# 28pins_sch.net
KiCad netlist of a schematic drawn in Altium Designer
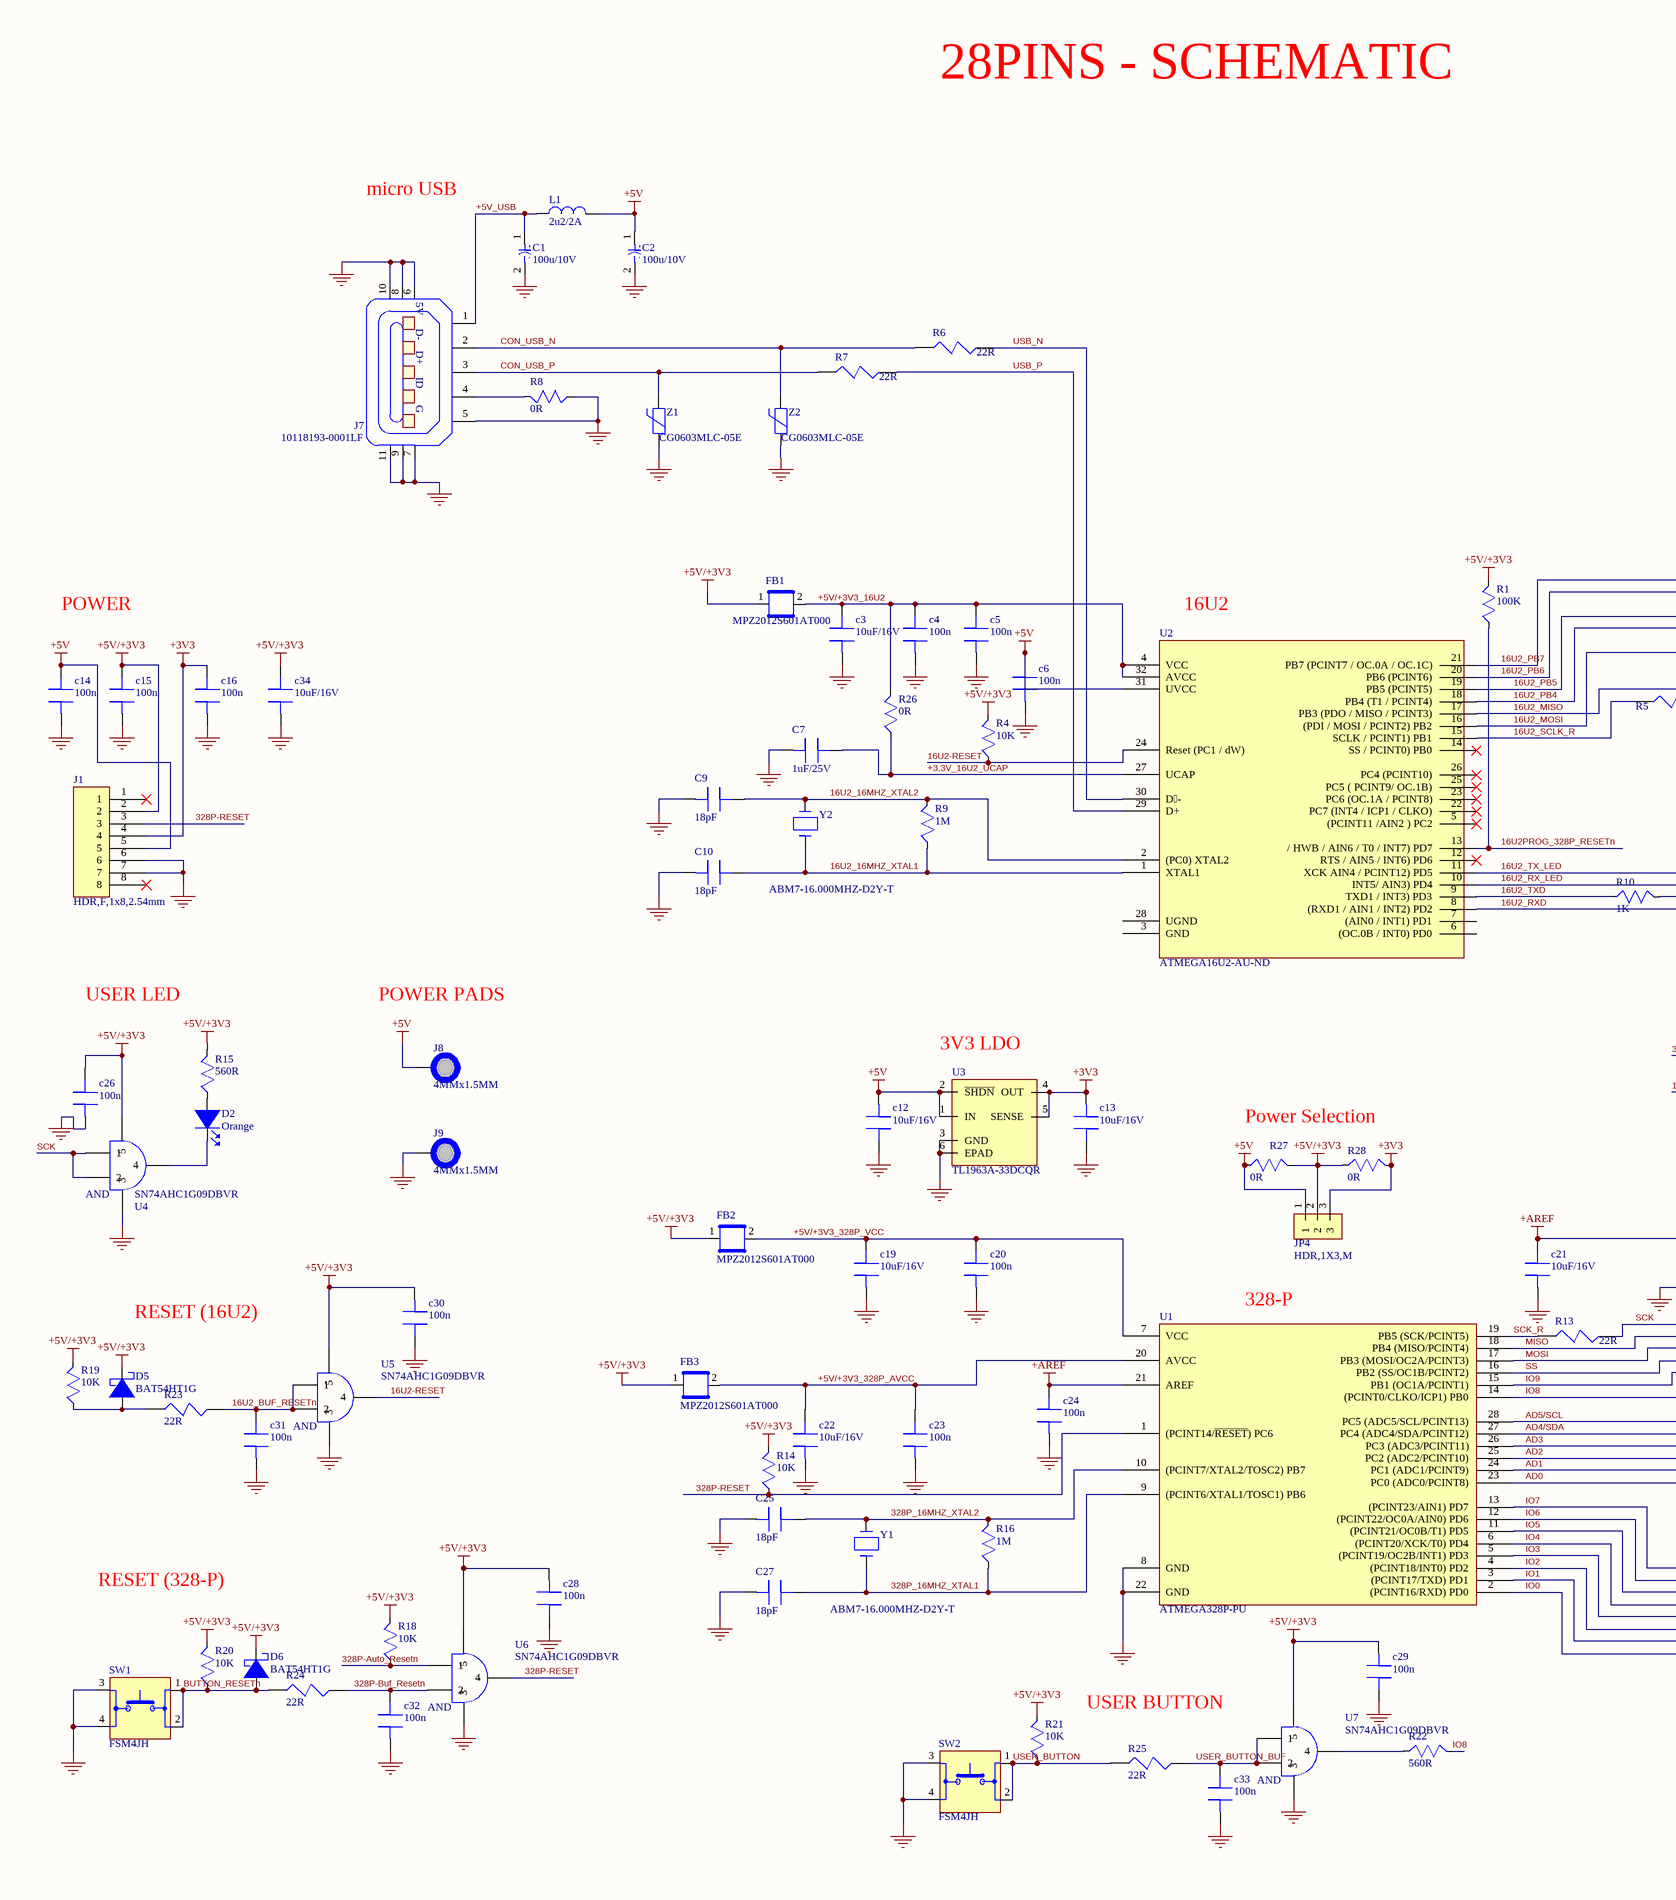
[diagram p0: 28pins_sch.SchDoc, left]
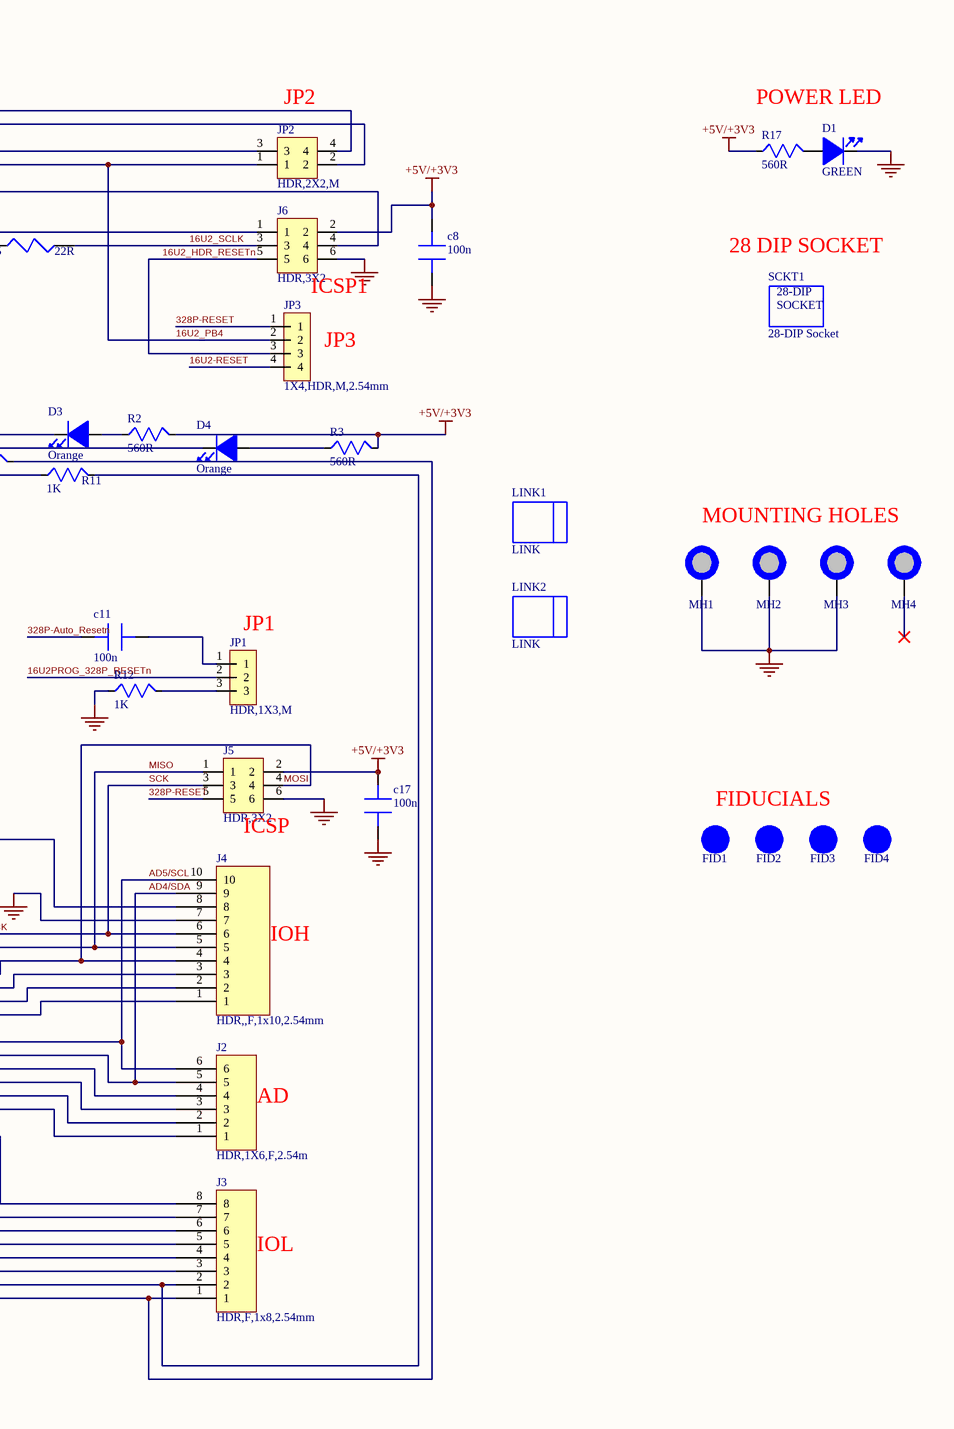
[diagram p1: 28pins_sch.SchDoc, right]

(export (version "E")
  (design (tool "Eeschema 10.0.6"))
  (components
    (comp (ref "C1")
      (value "100u/10V")
      (footprint "C_ALUM")
      (fields
        (field (name "MANUFACTURER") "Panasonic")
        (field (name "MANUFACTURER PART NUMBER") "EEE-1AA101WR")
      )
      (libsource (lib "28pins_Schlib1") (part "EEE-1AA101WR"))
    )
    (comp (ref "C2")
      (value "100u/10V")
      (footprint "C_ALUM")
      (fields
        (field (name "MANUFACTURER") "Panasonic")
        (field (name "MANUFACTURER PART NUMBER") "EEE-1AA101WR")
      )
      (libsource (lib "28pins_Schlib1") (part "EEE-1AA101WR"))
    )
    (comp (ref "c3")
      (value "10uF/16V")
      (footprint "X5R 0805")
      (fields
        (field (name "MANUFACTURER") "TDK")
        (field (name "MANUFACTURER PART NUMBER") "C2012X5R1C106K085AC")
      )
      (libsource (lib "28pins_Schlib1") (part "C2012X5R1C106K085AC"))
    )
    (comp (ref "c4")
      (value "100n")
      (footprint "C0805")
      (fields
        (field (name "MANUFACTURER") "Samsung")
        (field (name "MANUFACTURER PART NUMBER") "CL21B104KBCNNNC")
      )
      (libsource (lib "28pins_Schlib1") (part "CL21B104KBCNNNC"))
    )
    (comp (ref "c5")
      (value "100n")
      (footprint "C0805")
      (fields
        (field (name "MANUFACTURER") "Samsung")
        (field (name "MANUFACTURER PART NUMBER") "CL21B104KBCNNNC")
      )
      (libsource (lib "28pins_Schlib1") (part "CL21B104KBCNNNC"))
    )
    (comp (ref "c6")
      (value "100n")
      (footprint "C0805")
      (fields
        (field (name "MANUFACTURER") "Samsung")
        (field (name "MANUFACTURER PART NUMBER") "CL21B104KBCNNNC")
      )
      (libsource (lib "28pins_Schlib1") (part "CL21B104KBCNNNC"))
    )
    (comp (ref "C7")
      (value "1uF/25V")
      (footprint "C0805")
      (fields
        (field (name "MANUFACTURER") "TDK")
        (field (name "MANUFACTURER PART NUMBER") "C2012X5R1E105K125AA")
      )
      (libsource (lib "28pins_Schlib1") (part "C2012X5R1E105K125AA"))
    )
    (comp (ref "c8")
      (value "100n")
      (footprint "C0805")
      (fields
        (field (name "MANUFACTURER") "Samsung")
        (field (name "MANUFACTURER PART NUMBER") "CL21B104KBCNNNC")
      )
      (libsource (lib "28pins_Schlib1") (part "CL21B104KBCNNNC"))
    )
    (comp (ref "C9")
      (value "18pF")
      (footprint "C0805")
      (fields
        (field (name "MANUFACTURER") "KEMET")
        (field (name "MANUFACTURER PART NUMBER") "C0805C180K5RACTU")
      )
      (libsource (lib "28pins_Schlib1") (part "C0805C180K5RACTU"))
    )
    (comp (ref "C10")
      (value "18pF")
      (footprint "C0805")
      (fields
        (field (name "MANUFACTURER") "KEMET")
        (field (name "MANUFACTURER PART NUMBER") "C0805C180K5RACTU")
      )
      (libsource (lib "28pins_Schlib1") (part "C0805C180K5RACTU"))
    )
    (comp (ref "c11")
      (value "100n")
      (footprint "C0805")
      (fields
        (field (name "MANUFACTURER") "Samsung")
        (field (name "MANUFACTURER PART NUMBER") "CL21B104KBCNNNC")
      )
      (libsource (lib "28pins_Schlib1") (part "CL21B104KBCNNNC"))
    )
    (comp (ref "c12")
      (value "10uF/16V")
      (footprint "X5R 0805")
      (fields
        (field (name "MANUFACTURER") "TDK")
        (field (name "MANUFACTURER PART NUMBER") "C2012X5R1C106K085AC")
      )
      (libsource (lib "28pins_Schlib1") (part "C2012X5R1C106K085AC"))
    )
    (comp (ref "c13")
      (value "10uF/16V")
      (footprint "X5R 0805")
      (fields
        (field (name "MANUFACTURER") "TDK")
        (field (name "MANUFACTURER PART NUMBER") "C2012X5R1C106K085AC")
      )
      (libsource (lib "28pins_Schlib1") (part "C2012X5R1C106K085AC"))
    )
    (comp (ref "c14")
      (value "100n")
      (footprint "C0805")
      (fields
        (field (name "MANUFACTURER") "Samsung")
        (field (name "MANUFACTURER PART NUMBER") "CL21B104KBCNNNC")
      )
      (libsource (lib "28pins_Schlib1") (part "CL21B104KBCNNNC"))
    )
    (comp (ref "c15")
      (value "100n")
      (footprint "C0805")
      (fields
        (field (name "MANUFACTURER") "Samsung")
        (field (name "MANUFACTURER PART NUMBER") "CL21B104KBCNNNC")
      )
      (libsource (lib "28pins_Schlib1") (part "CL21B104KBCNNNC"))
    )
    (comp (ref "c16")
      (value "100n")
      (footprint "C0805")
      (fields
        (field (name "MANUFACTURER") "Samsung")
        (field (name "MANUFACTURER PART NUMBER") "CL21B104KBCNNNC")
      )
      (libsource (lib "28pins_Schlib1") (part "CL21B104KBCNNNC"))
    )
    (comp (ref "c17")
      (value "100n")
      (footprint "C0805")
      (fields
        (field (name "MANUFACTURER") "Samsung")
        (field (name "MANUFACTURER PART NUMBER") "CL21B104KBCNNNC")
      )
      (libsource (lib "28pins_Schlib1") (part "CL21B104KBCNNNC"))
    )
    (comp (ref "c19")
      (value "10uF/16V")
      (footprint "X5R 0805")
      (fields
        (field (name "MANUFACTURER") "TDK")
        (field (name "MANUFACTURER PART NUMBER") "C2012X5R1C106K085AC")
      )
      (libsource (lib "28pins_Schlib1") (part "C2012X5R1C106K085AC"))
    )
    (comp (ref "c20")
      (value "100n")
      (footprint "C0805")
      (fields
        (field (name "MANUFACTURER") "Samsung")
        (field (name "MANUFACTURER PART NUMBER") "CL21B104KBCNNNC")
      )
      (libsource (lib "28pins_Schlib1") (part "CL21B104KBCNNNC"))
    )
    (comp (ref "c21")
      (value "10uF/16V")
      (footprint "X5R 0805")
      (fields
        (field (name "MANUFACTURER") "TDK")
        (field (name "MANUFACTURER PART NUMBER") "C2012X5R1C106K085AC")
      )
      (libsource (lib "28pins_Schlib1") (part "C2012X5R1C106K085AC"))
    )
    (comp (ref "c22")
      (value "10uF/16V")
      (footprint "X5R 0805")
      (fields
        (field (name "MANUFACTURER") "TDK")
        (field (name "MANUFACTURER PART NUMBER") "C2012X5R1C106K085AC")
      )
      (libsource (lib "28pins_Schlib1") (part "C2012X5R1C106K085AC"))
    )
    (comp (ref "c23")
      (value "100n")
      (footprint "C0805")
      (fields
        (field (name "MANUFACTURER") "Samsung")
        (field (name "MANUFACTURER PART NUMBER") "CL21B104KBCNNNC")
      )
      (libsource (lib "28pins_Schlib1") (part "CL21B104KBCNNNC"))
    )
    (comp (ref "c24")
      (value "100n")
      (footprint "C0805")
      (fields
        (field (name "MANUFACTURER") "Samsung")
        (field (name "MANUFACTURER PART NUMBER") "CL21B104KBCNNNC")
      )
      (libsource (lib "28pins_Schlib1") (part "CL21B104KBCNNNC"))
    )
    (comp (ref "C25")
      (value "18pF")
      (footprint "C0805")
      (fields
        (field (name "MANUFACTURER") "KEMET")
        (field (name "MANUFACTURER PART NUMBER") "C0805C180K5RACTU")
      )
      (libsource (lib "28pins_Schlib1") (part "C0805C180K5RACTU"))
    )
    (comp (ref "c26")
      (value "100n")
      (footprint "C0805")
      (fields
        (field (name "MANUFACTURER") "Samsung")
        (field (name "MANUFACTURER PART NUMBER") "CL21B104KBCNNNC")
      )
      (libsource (lib "28pins_Schlib1") (part "CL21B104KBCNNNC"))
    )
    (comp (ref "C27")
      (value "18pF")
      (footprint "C0805")
      (fields
        (field (name "MANUFACTURER") "KEMET")
        (field (name "MANUFACTURER PART NUMBER") "C0805C180K5RACTU")
      )
      (libsource (lib "28pins_Schlib1") (part "C0805C180K5RACTU"))
    )
    (comp (ref "c28")
      (value "100n")
      (footprint "C0805")
      (fields
        (field (name "MANUFACTURER") "Samsung")
        (field (name "MANUFACTURER PART NUMBER") "CL21B104KBCNNNC")
      )
      (libsource (lib "28pins_Schlib1") (part "CL21B104KBCNNNC"))
    )
    (comp (ref "c29")
      (value "100n")
      (footprint "C0805")
      (fields
        (field (name "MANUFACTURER") "Samsung")
        (field (name "MANUFACTURER PART NUMBER") "CL21B104KBCNNNC")
      )
      (libsource (lib "28pins_Schlib1") (part "CL21B104KBCNNNC"))
    )
    (comp (ref "c30")
      (value "100n")
      (footprint "C0805")
      (fields
        (field (name "MANUFACTURER") "Samsung")
        (field (name "MANUFACTURER PART NUMBER") "CL21B104KBCNNNC")
      )
      (libsource (lib "28pins_Schlib1") (part "CL21B104KBCNNNC"))
    )
    (comp (ref "c31")
      (value "100n")
      (footprint "C0805")
      (fields
        (field (name "MANUFACTURER") "Samsung")
        (field (name "MANUFACTURER PART NUMBER") "CL21B104KBCNNNC")
      )
      (libsource (lib "28pins_Schlib1") (part "CL21B104KBCNNNC"))
    )
    (comp (ref "c32")
      (value "100n")
      (footprint "C0805")
      (fields
        (field (name "MANUFACTURER") "Samsung")
        (field (name "MANUFACTURER PART NUMBER") "CL21B104KBCNNNC")
      )
      (libsource (lib "28pins_Schlib1") (part "CL21B104KBCNNNC"))
    )
    (comp (ref "c33")
      (value "100n")
      (footprint "C0805")
      (fields
        (field (name "MANUFACTURER") "Samsung")
        (field (name "MANUFACTURER PART NUMBER") "CL21B104KBCNNNC")
      )
      (libsource (lib "28pins_Schlib1") (part "CL21B104KBCNNNC"))
    )
    (comp (ref "c34")
      (value "10uF/16V")
      (footprint "X5R 0805")
      (fields
        (field (name "MANUFACTURER") "TDK")
        (field (name "MANUFACTURER PART NUMBER") "C2012X5R1C106K085AC")
      )
      (libsource (lib "28pins_Schlib1") (part "C2012X5R1C106K085AC"))
    )
    (comp (ref "D1")
      (value "GREEN")
      (footprint "LED_0603")
      (description "Single Color LED")
      (fields
        (field (name "MANUFACTURER") "SunLED")
        (field (name "MANUFACTURER PART NUMBER") "XZCDGK53W-8VF")
      )
      (libsource (lib "28pins_Schlib1") (part "XZCDGK53W-8VF"))
    )
    (comp (ref "D2")
      (value "Orange")
      (footprint "LED_0603")
      (description "Single Color LED Array, Orange, Transparent Clear, 1.2mm")
      (fields (field (name "MANUFACTURER") "Rohm") (field (name "MANUFACTURER PART NUMBER") "SML-311DTT86"))
      (libsource (lib "28pins_Schlib1") (part "SML-311DTT86"))
    )
    (comp (ref "D3")
      (value "Orange")
      (footprint "LED_0603")
      (description "Single Color LED Array, Orange, Transparent Clear, 1.2mm")
      (fields (field (name "MANUFACTURER") "Rohm") (field (name "MANUFACTURER PART NUMBER") "SML-311DTT86"))
      (libsource (lib "28pins_Schlib1") (part "SML-311DTT86"))
    )
    (comp (ref "D4")
      (value "Orange")
      (footprint "LED_0603")
      (description "Single Color LED Array, Orange, Transparent Clear, 1.2mm")
      (fields (field (name "MANUFACTURER") "Rohm") (field (name "MANUFACTURER PART NUMBER") "SML-311DTT86"))
      (libsource (lib "28pins_Schlib1") (part "SML-311DTT86"))
    )
    (comp (ref "D5")
      (value "BAT54HT1G")
      (footprint "SOD323")
      (description "Rectifier Diode, 1 Phase, 1 Element, 0.2A, 30V V(RRM), Silicon")
      (fields (field (name "MANUFACTURER") "ON Semiconductor / Fairchild"))
      (libsource (lib "28pins_Schlib1") (part "BAT54HT1G"))
    )
    (comp (ref "D6")
      (value "BAT54HT1G")
      (footprint "SOD323")
      (description "Rectifier Diode, 1 Phase, 1 Element, 0.2A, 30V V(RRM), Silicon")
      (fields (field (name "MANUFACTURER") "ON Semiconductor / Fairchild"))
      (libsource (lib "28pins_Schlib1") (part "BAT54HT1G"))
    )
    (comp (ref "FB1")
      (value "MPZ2012S601AT000")
      (footprint "C0805")
      (description "Ferrite Chip, 1 Function(s), 2A")
      (fields (field (name "MANUFACTURER") "TDK"))
      (libsource (lib "28pins_Schlib1") (part "MPZ2012S601AT000"))
    )
    (comp (ref "FB2")
      (value "MPZ2012S601AT000")
      (footprint "C0805")
      (description "Ferrite Chip, 1 Function(s), 2A")
      (fields (field (name "MANUFACTURER") "TDK"))
      (libsource (lib "28pins_Schlib1") (part "MPZ2012S601AT000"))
    )
    (comp (ref "FB3")
      (value "MPZ2012S601AT000")
      (footprint "C0805")
      (description "Ferrite Chip, 1 Function(s), 2A")
      (fields (field (name "MANUFACTURER") "TDK"))
      (libsource (lib "28pins_Schlib1") (part "MPZ2012S601AT000"))
    )
    (comp (ref "FID1")
      (value "1MMC")
      (footprint "FID _40x120D")
      (description "Fiducial 45mm Diameter, 120 mil mask")
      (libsource (lib "28pins_Schlib1") (part "FID_1MMC"))
    )
    (comp (ref "FID2")
      (value "1MMC")
      (footprint "FID _40x120D")
      (description "Fiducial 45mm Diameter, 120 mil mask")
      (libsource (lib "28pins_Schlib1") (part "FID_1MMC"))
    )
    (comp (ref "FID3")
      (value "1MMC")
      (footprint "FID _40x120D")
      (description "Fiducial 45mm Diameter, 120 mil mask")
      (libsource (lib "28pins_Schlib1") (part "FID_1MMC"))
    )
    (comp (ref "FID4")
      (value "1MMC")
      (footprint "FID _40x120D")
      (description "Fiducial 45mm Diameter, 120 mil mask")
      (libsource (lib "28pins_Schlib1") (part "FID_1MMC"))
    )
    (comp (ref "J1")
      (value "HDR,F,1x8,2.54mm")
      (footprint "HDR,F,1X8,2.54mm")
      (fields (field (name "MANUFACTURER") "Harwin") (field (name "MANUFACTURER PART NUMBER") "M20-7820842"))
      (libsource (lib "") (part "M20-7820842_1"))
    )
    (comp (ref "J2")
      (value "HDR,1X6,F,2.54m")
      (footprint "HDR,1X6,F,2.54mm")
      (fields (field (name "MANUFACTURER") "Harwin") (field (name "MANUFACTURER PART NUMBER") "M20-7820646"))
      (libsource (lib "28pins_Schlib1") (part "M20-7820646"))
    )
    (comp (ref "J3")
      (value "HDR,F,1x8,2.54mm")
      (footprint "HDR,F,1X8,2.54mm")
      (fields (field (name "MANUFACTURER") "Harwin") (field (name "MANUFACTURER PART NUMBER") "M20-7820842"))
      (libsource (lib "28pins_Schlib1") (part "M20-7820842"))
    )
    (comp (ref "J4")
      (value "HDR,,F,1x10,2.54mm")
      (footprint "HDR,F,1x10,2.54mm")
      (fields (field (name "MANUFACTURER") "Harwin") (field (name "MANUFACTURER PART NUMBER") "M20-7821046"))
      (libsource (lib "28pins_Schlib1") (part "M20-7821046"))
    )
    (comp (ref "J5")
      (value "HDR,3X2")
      (footprint "HDR,2X3,2.54mm")
      (description "Conn Unshrouded Header HDR 6 POS 2.54mm Solder ST Top Entry Thru-Hole BergStik® Bulk")
      (fields
        (field (name "MANUFACTURER") "Amphenol ICC / FCI")
        (field (name "MANUFACTURER PART NUMBER") "67997-106HLF")
      )
      (libsource (lib "28pins_Schlib1") (part "67997-106HLF"))
    )
    (comp (ref "J6")
      (value "HDR,3X2")
      (footprint "HDR,2X3,2.54mm")
      (description "Conn Unshrouded Header HDR 6 POS 2.54mm Solder ST Top Entry Thru-Hole BergStik® Bulk")
      (fields
        (field (name "MANUFACTURER") "Amphenol ICC / FCI")
        (field (name "MANUFACTURER PART NUMBER") "67997-106HLF")
      )
      (libsource (lib "28pins_Schlib1") (part "67997-106HLF"))
    )
    (comp (ref "J7")
      (value "10118193-0001LF")
      (footprint "10118193")
      (description "FCI Right Angle Surface Mount Mount Female USB Connector; 100 V ac; 1.8A")
      (fields (field (name "MANUFACTURER") "Amphenol ICC / FCI"))
      (libsource (lib "28pins_Schlib1") (part "10118193-0001LF"))
    )
    (comp (ref "J8")
      (value "4MMx1.5MM")
      (footprint "pad_with_holes_4MMx1.5MM")
      (description "pad with holes, 4MMx1.5MM")
      (libsource (lib "28pins_Schlib1") (part "pad_with_hole_4MMx1.5MM"))
    )
    (comp (ref "J9")
      (value "4MMx1.5MM")
      (footprint "pad_with_holes_4MMx1.5MM")
      (description "pad with holes, 4MMx1.5MM")
      (libsource (lib "28pins_Schlib1") (part "pad_with_hole_4MMx1.5MM"))
    )
    (comp (ref "JP1")
      (value "HDR,1X3,M")
      (footprint "HDR,1X3,M,2.54mm")
      (description "Conn Unshrouded Header HDR 3 POS 2.54mm Solder ST Top Entry Thru-Hole BergStik® Automotive Bulk")
      (fields
        (field (name "MANUFACTURER") "Amphenol ICC / FCI")
        (field (name "MANUFACTURER PART NUMBER") "68000-103HLF")
      )
      (libsource (lib "28pins_Schlib1") (part "68000-103HLF"))
    )
    (comp (ref "JP2")
      (value "HDR,2X2,M")
      (footprint "HDR,2X2,2.54mm")
      (description "Conn Unshrouded Header HDR 4 POS 2.54mm Solder ST Top Entry Thru-Hole BergStik® Bulk")
      (fields
        (field (name "MANUFACTURER") "Amphenol ICC / FCI")
        (field (name "MANUFACTURER PART NUMBER") "67996-104HLF")
      )
      (libsource (lib "28pins_Schlib1") (part "67996-104HLF"))
    )
    (comp (ref "JP3")
      (value "1X4,HDR,M,2.54mm")
      (footprint "HDR,1X4,M,2.54mm")
      (description "Conn Unshrouded Header HDR 4 POS 2.54mm Solder ST Thru-Hole Bag")
      (fields
        (field (name "MANUFACTURER") "Amphenol ICC / FCI")
        (field (name "MANUFACTURER PART NUMBER") "68001-204HLF")
      )
      (libsource (lib "28pins_Schlib1") (part "68001-204HLF"))
    )
    (comp (ref "JP4")
      (value "HDR,1X3,M")
      (footprint "HDR,1X3,M,2.54mm")
      (description "Conn Unshrouded Header HDR 3 POS 2.54mm Solder ST Top Entry Thru-Hole BergStik® Automotive Bulk")
      (fields
        (field (name "MANUFACTURER") "Amphenol ICC / FCI")
        (field (name "MANUFACTURER PART NUMBER") "68000-103HLF")
      )
      (libsource (lib "") (part "68000-103HLF_1"))
    )
    (comp (ref "L1")
      (value "2u2/2A")
      (footprint "INDUCTOR")
      (description "General Purpose Inductor, 2.2uH, 20%, 1 Element, Metal Composite-Core, SMD")
      (fields
        (field (name "MANUFACTURER") "Samsung")
        (field (name "MANUFACTURER PART NUMBER") "CIGT252008LM2R2MNE")
      )
      (libsource (lib "28pins_Schlib1") (part "CIGT252008LM2R2MNE"))
    )
    (comp (ref "LINK1")
      (value "LINK")
      (description "Shunts/Jumper Connector")
      (fields
        (field (name "MANUFACTURER") "Sullins")
        (field (name "MANUFACTURER PART NUMBER") "QPC02SXGN-RC")
      )
      (libsource (lib "28pins_Schlib1") (part "QPC02SXGN-RC"))
    )
    (comp (ref "LINK2")
      (value "LINK")
      (description "Shunts/Jumper Connector")
      (fields
        (field (name "MANUFACTURER") "Sullins")
        (field (name "MANUFACTURER PART NUMBER") "QPC02SXGN-RC")
      )
      (libsource (lib "28pins_Schlib1") (part "QPC02SXGN-RC"))
    )
    (comp (ref "MH1")
      (value "MH_7.4MM,drill")
      (footprint "MH_7.4MM")
      (libsource (lib "28pins_Schlib1") (part "MH_7.4MM"))
    )
    (comp (ref "MH2")
      (value "MH_7.4MM,drill")
      (footprint "MH_7.4MM")
      (libsource (lib "28pins_Schlib1") (part "MH_7.4MM"))
    )
    (comp (ref "MH3")
      (value "MH_7.4MM,drill")
      (footprint "MH_7.4MM")
      (libsource (lib "28pins_Schlib1") (part "MH_7.4MM"))
    )
    (comp (ref "MH4")
      (value "MH_7.4_noncoppper_nonplated")
      (footprint "MH7.44_nonplated_nonecopper")
      (libsource (lib "28pins_Schlib1") (part "MH_7.44_noncopper_nonplated"))
    )
    (comp (ref "R1")
      (value "100K")
      (footprint "R0805")
      (fields
        (field (name "MANUFACTURER") "Yageo")
        (field (name "MANUFACTURER PART NUMBER") "AC0805FR-13100KL")
        (field (name "TOLERANCE") "1%")
      )
      (libsource (lib "28pins_Schlib1") (part "AC0805FR-13100KL"))
    )
    (comp (ref "R2")
      (value "560R")
      (footprint "R0805")
      (fields
        (field (name "MANUFACTURER") "Yageo")
        (field (name "MANUFACTURER PART NUMBER") "RC0805FR-10560RL")
        (field (name "TOLERANCE") "1%")
      )
      (libsource (lib "28pins_Schlib1") (part "RC0805FR-10560RL"))
    )
    (comp (ref "R3")
      (value "560R")
      (footprint "R0805")
      (fields
        (field (name "MANUFACTURER") "Yageo")
        (field (name "MANUFACTURER PART NUMBER") "RC0805FR-10560RL")
        (field (name "TOLERANCE") "1%")
      )
      (libsource (lib "28pins_Schlib1") (part "RC0805FR-10560RL"))
    )
    (comp (ref "R4")
      (value "10K")
      (footprint "R0805")
      (fields
        (field (name "MANUFACTURER") "Yageo")
        (field (name "MANUFACTURER PART NUMBER") "RC0805FR-0710KL")
        (field (name "TOLERANCE") "1%")
      )
      (libsource (lib "28pins_Schlib1") (part "RC0805FR-0710KL"))
    )
    (comp (ref "R5")
      (value "22R")
      (footprint "R0805")
      (fields
        (field (name "MANUFACTURER") "Yageo")
        (field (name "MANUFACTURER PART NUMBER") "AC0805FR-0722RL")
        (field (name "TOLERANCE") "1%")
      )
      (libsource (lib "28pins_Schlib1") (part "AC0805FR-0722RL"))
    )
    (comp (ref "R6")
      (value "22R")
      (footprint "R0805")
      (fields
        (field (name "MANUFACTURER") "Yageo")
        (field (name "MANUFACTURER PART NUMBER") "AC0805FR-0722RL")
        (field (name "TOLERANCE") "1%")
      )
      (libsource (lib "28pins_Schlib1") (part "AC0805FR-0722RL"))
    )
    (comp (ref "R7")
      (value "22R")
      (footprint "R0805")
      (fields
        (field (name "MANUFACTURER") "Yageo")
        (field (name "MANUFACTURER PART NUMBER") "AC0805FR-0722RL")
        (field (name "TOLERANCE") "1%")
      )
      (libsource (lib "28pins_Schlib1") (part "AC0805FR-0722RL"))
    )
    (comp (ref "R8")
      (value "0R")
      (footprint "R0805")
      (description "Metal Glaze/thick Film, 0.125W, 0ohm, Surface Mount, 0805")
      (fields
        (field (name "MANUFACTURER") "Yageo")
        (field (name "MANUFACTURER PART NUMBER") "RC0805JR-070RL")
      )
      (libsource (lib "28pins_Schlib1") (part "RC0805JR-070RL"))
    )
    (comp (ref "R9")
      (value "1M")
      (footprint "R0805")
      (fields
        (field (name "MANUFACTURER") "Yageo")
        (field (name "MANUFACTURER PART NUMBER") "RC0805FR-071ML")
        (field (name "TOLERANCE") "1%")
      )
      (libsource (lib "28pins_Schlib1") (part "RC0805FR-071ML"))
    )
    (comp (ref "R10")
      (value "1K")
      (footprint "R0805")
      (fields
        (field (name "MANUFACTURER") "Yageo")
        (field (name "MANUFACTURER PART NUMBER") "RC0805FR-071KL")
        (field (name "TOLERANCE") "1%")
      )
      (libsource (lib "28pins_Schlib1") (part "RC0805FR-071KL"))
    )
    (comp (ref "R11")
      (value "1K")
      (footprint "R0805")
      (fields
        (field (name "MANUFACTURER") "Yageo")
        (field (name "MANUFACTURER PART NUMBER") "RC0805FR-071KL")
        (field (name "TOLERANCE") "1%")
      )
      (libsource (lib "28pins_Schlib1") (part "RC0805FR-071KL"))
    )
    (comp (ref "R12")
      (value "1K")
      (footprint "R0805")
      (fields
        (field (name "MANUFACTURER") "Yageo")
        (field (name "MANUFACTURER PART NUMBER") "RC0805FR-071KL")
        (field (name "TOLERANCE") "1%")
      )
      (libsource (lib "28pins_Schlib1") (part "RC0805FR-071KL"))
    )
    (comp (ref "R13")
      (value "22R")
      (footprint "R0805")
      (fields
        (field (name "MANUFACTURER") "Yageo")
        (field (name "MANUFACTURER PART NUMBER") "AC0805FR-0722RL")
        (field (name "TOLERANCE") "1%")
      )
      (libsource (lib "28pins_Schlib1") (part "AC0805FR-0722RL"))
    )
    (comp (ref "R14")
      (value "10K")
      (footprint "R0805")
      (fields
        (field (name "MANUFACTURER") "Yageo")
        (field (name "MANUFACTURER PART NUMBER") "RC0805FR-0710KL")
        (field (name "TOLERANCE") "1%")
      )
      (libsource (lib "28pins_Schlib1") (part "RC0805FR-0710KL"))
    )
    (comp (ref "R15")
      (value "560R")
      (footprint "R0805")
      (fields
        (field (name "MANUFACTURER") "Yageo")
        (field (name "MANUFACTURER PART NUMBER") "RC0805FR-10560RL")
        (field (name "TOLERANCE") "1%")
      )
      (libsource (lib "28pins_Schlib1") (part "RC0805FR-10560RL"))
    )
    (comp (ref "R16")
      (value "1M")
      (footprint "R0805")
      (fields
        (field (name "MANUFACTURER") "Yageo")
        (field (name "MANUFACTURER PART NUMBER") "RC0805FR-071ML")
        (field (name "TOLERANCE") "1%")
      )
      (libsource (lib "28pins_Schlib1") (part "RC0805FR-071ML"))
    )
    (comp (ref "R17")
      (value "560R")
      (footprint "R0805")
      (fields
        (field (name "MANUFACTURER") "Yageo")
        (field (name "MANUFACTURER PART NUMBER") "RC0805FR-10560RL")
        (field (name "TOLERANCE") "1%")
      )
      (libsource (lib "28pins_Schlib1") (part "RC0805FR-10560RL"))
    )
    (comp (ref "R18")
      (value "10K")
      (footprint "R0805")
      (fields
        (field (name "MANUFACTURER") "Yageo")
        (field (name "MANUFACTURER PART NUMBER") "RC0805FR-0710KL")
        (field (name "TOLERANCE") "1%")
      )
      (libsource (lib "28pins_Schlib1") (part "RC0805FR-0710KL"))
    )
    (comp (ref "R19")
      (value "10K")
      (footprint "R0805")
      (fields
        (field (name "MANUFACTURER") "Yageo")
        (field (name "MANUFACTURER PART NUMBER") "RC0805FR-0710KL")
        (field (name "TOLERANCE") "1%")
      )
      (libsource (lib "28pins_Schlib1") (part "RC0805FR-0710KL"))
    )
    (comp (ref "R20")
      (value "10K")
      (footprint "R0805")
      (fields
        (field (name "MANUFACTURER") "Yageo")
        (field (name "MANUFACTURER PART NUMBER") "RC0805FR-0710KL")
        (field (name "TOLERANCE") "1%")
      )
      (libsource (lib "28pins_Schlib1") (part "RC0805FR-0710KL"))
    )
    (comp (ref "R21")
      (value "10K")
      (footprint "R0805")
      (fields
        (field (name "MANUFACTURER") "Yageo")
        (field (name "MANUFACTURER PART NUMBER") "RC0805FR-0710KL")
        (field (name "TOLERANCE") "1%")
      )
      (libsource (lib "28pins_Schlib1") (part "RC0805FR-0710KL"))
    )
    (comp (ref "R22")
      (value "560R")
      (footprint "R0805")
      (fields
        (field (name "MANUFACTURER") "Yageo")
        (field (name "MANUFACTURER PART NUMBER") "RC0805FR-10560RL")
        (field (name "TOLERANCE") "1%")
      )
      (libsource (lib "28pins_Schlib1") (part "RC0805FR-10560RL"))
    )
    (comp (ref "R23")
      (value "22R")
      (footprint "R0805")
      (fields
        (field (name "MANUFACTURER") "Yageo")
        (field (name "MANUFACTURER PART NUMBER") "AC0805FR-0722RL")
        (field (name "TOLERANCE") "1%")
      )
      (libsource (lib "28pins_Schlib1") (part "AC0805FR-0722RL"))
    )
    (comp (ref "R24")
      (value "22R")
      (footprint "R0805")
      (fields
        (field (name "MANUFACTURER") "Yageo")
        (field (name "MANUFACTURER PART NUMBER") "AC0805FR-0722RL")
        (field (name "TOLERANCE") "1%")
      )
      (libsource (lib "28pins_Schlib1") (part "AC0805FR-0722RL"))
    )
    (comp (ref "R25")
      (value "22R")
      (footprint "R0805")
      (fields
        (field (name "MANUFACTURER") "Yageo")
        (field (name "MANUFACTURER PART NUMBER") "AC0805FR-0722RL")
        (field (name "TOLERANCE") "1%")
      )
      (libsource (lib "28pins_Schlib1") (part "AC0805FR-0722RL"))
    )
    (comp (ref "R26")
      (value "0R")
      (footprint "R0805")
      (description "Metal Glaze/thick Film, 0.125W, 0ohm, Surface Mount, 0805")
      (fields
        (field (name "MANUFACTURER") "Yageo")
        (field (name "MANUFACTURER PART NUMBER") "RC0805JR-070RL")
      )
      (libsource (lib "28pins_Schlib1") (part "RC0805JR-070RL"))
    )
    (comp (ref "R27")
      (value "0R")
      (footprint "R0805")
      (description "Metal Glaze/thick Film, 0.125W, 0ohm, Surface Mount, 0805")
      (fields
        (field (name "MANUFACTURER") "Yageo")
        (field (name "MANUFACTURER PART NUMBER") "RC0805JR-070RL")
      )
      (libsource (lib "28pins_Schlib1") (part "RC0805JR-070RL"))
    )
    (comp (ref "R28")
      (value "0R")
      (footprint "R0805")
      (description "Metal Glaze/thick Film, 0.125W, 0ohm, Surface Mount, 0805")
      (fields
        (field (name "MANUFACTURER") "Yageo")
        (field (name "MANUFACTURER PART NUMBER") "RC0805JR-070RL")
      )
      (libsource (lib "28pins_Schlib1") (part "RC0805JR-070RL"))
    )
    (comp (ref "SCKT1")
      (value "28-DIP Socket")
      (footprint "28_DIP_SCKT")
      (description "IC Socket, DIP28, 28 Contact(s)")
      (fields (field (name "MANUFACTURER") "3M") (field (name "MANUFACTURER PART NUMBER") "4828-3004-CP"))
      (libsource (lib "28pins_Schlib1") (part "4828-3004-CP"))
    )
    (comp (ref "SW1")
      (value "FSM4JH")
      (footprint "SW")
      (description "Keypad Switch, 1 Switches, Momentary-tactile, 0.05A, 1.57N, Solder Terminal, Through Hole-straight")
      (fields (field (name "MANUFACTURER") "TE Connectivity"))
      (libsource (lib "28pins_Schlib1") (part "FSM4JH"))
    )
    (comp (ref "SW2")
      (value "FSM4JH")
      (footprint "SW")
      (description "Keypad Switch, 1 Switches, Momentary-tactile, 0.05A, 1.57N, Solder Terminal, Through Hole-straight")
      (fields (field (name "MANUFACTURER") "TE Connectivity"))
      (libsource (lib "28pins_Schlib1") (part "FSM4JH"))
    )
    (comp (ref "U1")
      (value "ATMEGA328P-PU")
      (footprint "28_DIP_7.62mm")
      (description "RISC Microcontroller, 8-Bit, FLASH, AVR RISC CPU, 20MHz, CMOS, PDIP28")
      (fields (field (name "MANUFACTURER") "Microchip"))
      (libsource (lib "28pins_Schlib1") (part "ATMEGA328P-PU"))
    )
    (comp (ref "U2")
      (value "ATMEGA16U2-AU-ND")
      (footprint "TQFP32")
      (description "RISC Microcontroller, 8-Bit, FLASH, AVR RISC CPU, 16MHz, CMOS, PQFP32")
      (fields
        (field (name "MANUFACTURER") "Microchip")
        (field (name "MANUFACTURER PART NUMBER") "ATMEGA16U2-AU")
      )
      (libsource (lib "28pins_Schlib1") (part "ATMEGA16U2-AU"))
    )
    (comp (ref "U3")
      (value "TL1963A-33DCQR")
      (footprint "DCQ(R-PDSO-G6)")
      (description "Fixed Positive LDO Regulator, 3.3V, 0.55V Dropout, BIPolar, PDSO6")
      (fields (field (name "MANUFACTURER") "Texas Instruments"))
      (libsource (lib "28pins_Schlib1") (part "TL1963A-33DCQR"))
    )
    (comp (ref "U4")
      (value "SN74AHC1G09DBVR")
      (footprint "DBV_SOT")
      (description "AND Gate, AHC/VHC/H/U/V Series, 1-Func, 2-Input, CMOS, PDSO5")
      (fields (field (name "MANUFACTURER") "Texas Instruments"))
      (libsource (lib "28pins_Schlib1") (part "SN74AHC1G09DBVR"))
    )
    (comp (ref "U5")
      (value "SN74AHC1G09DBVR")
      (footprint "DBV_SOT")
      (description "AND Gate, AHC/VHC/H/U/V Series, 1-Func, 2-Input, CMOS, PDSO5")
      (fields (field (name "MANUFACTURER") "Texas Instruments"))
      (libsource (lib "28pins_Schlib1") (part "SN74AHC1G09DBVR"))
    )
    (comp (ref "U6")
      (value "SN74AHC1G09DBVR")
      (footprint "DBV_SOT")
      (description "AND Gate, AHC/VHC/H/U/V Series, 1-Func, 2-Input, CMOS, PDSO5")
      (fields (field (name "MANUFACTURER") "Texas Instruments"))
      (libsource (lib "28pins_Schlib1") (part "SN74AHC1G09DBVR"))
    )
    (comp (ref "U7")
      (value "SN74AHC1G09DBVR")
      (footprint "DBV_SOT")
      (description "AND Gate, AHC/VHC/H/U/V Series, 1-Func, 2-Input, CMOS, PDSO5")
      (fields (field (name "MANUFACTURER") "Texas Instruments"))
      (libsource (lib "28pins_Schlib1") (part "SN74AHC1G09DBVR"))
    )
    (comp (ref "Y1")
      (value "ABM7-16.000MHZ-D2Y-T")
      (footprint "ABM7-16MHz,BIG")
      (description "Crystal 16MHz ±20ppm (Tol) ±30ppm (Stability) 18pF FUND 50Ohm 2-Pin Mini-CSMD T/R")
      (fields (field (name "MANUFACTURER") "Abracon"))
      (libsource (lib "28pins_Schlib1") (part "ABM7-16.000MHZ-D2Y-T"))
    )
    (comp (ref "Y2")
      (value "ABM7-16.000MHZ-D2Y-T")
      (footprint "ABM7-16MHz,BIG")
      (description "Crystal 16MHz ±20ppm (Tol) ±30ppm (Stability) 18pF FUND 50Ohm 2-Pin Mini-CSMD T/R")
      (fields (field (name "MANUFACTURER") "Abracon"))
      (libsource (lib "28pins_Schlib1") (part "ABM7-16.000MHZ-D2Y-T"))
    )
    (comp (ref "Z1")
      (value "CG0603MLC-05E")
      (footprint "R0603")
      (description "Varistor, 5V, Surface Mount")
      (fields (field (name "MANUFACTURER") "Bourns"))
      (libsource (lib "28pins_Schlib1") (part "CG0603MLC-05E"))
    )
    (comp (ref "Z2")
      (value "CG0603MLC-05E")
      (footprint "R0603")
      (description "Varistor, 5V, Surface Mount")
      (fields (field (name "MANUFACTURER") "Bourns"))
      (libsource (lib "28pins_Schlib1") (part "CG0603MLC-05E"))
    )
  )
  (nets
    (net (code "1") (name "+3V3") (class "Default")
      (node (ref "J1") (pin "4") (pinfunction "4_4") (pintype "passive"))
      (node (ref "JP4") (pin "3") (pinfunction "3_3") (pintype "passive"))
      (node (ref "R28") (pin "2") (pinfunction "2_2") (pintype "passive"))
      (node (ref "U3") (pin "4") (pinfunction "OUT_4") (pintype "passive"))
      (node (ref "U3") (pin "5") (pinfunction "SENSE_5") (pintype "passive"))
      (node (ref "c13") (pin "1") (pinfunction "1_1") (pintype "passive"))
      (node (ref "c16") (pin "2") (pinfunction "2_2") (pintype "passive"))
    )
    (net (code "2") (name "+5V") (class "Default")
      (node (ref "C2") (pin "1") (pinfunction "1_1") (pintype "passive"))
      (node (ref "J1") (pin "5") (pinfunction "5_5") (pintype "passive"))
      (node (ref "J8") (pin "1") (pinfunction "1_1") (pintype "open_collector"))
      (node (ref "JP4") (pin "1") (pinfunction "1_1") (pintype "passive"))
      (node (ref "L1") (pin "2") (pinfunction "2_2") (pintype "passive"))
      (node (ref "R27") (pin "1") (pinfunction "1_1") (pintype "passive"))
      (node (ref "U2") (pin "31") (pinfunction "UVCC_31") (pintype "passive"))
      (node (ref "U3") (pin "1") (pinfunction "IN_1") (pintype "passive"))
      (node (ref "U3") (pin "2") (pinfunction "~{SHDN}_2") (pintype "passive"))
      (node (ref "c12") (pin "1") (pinfunction "1_1") (pintype "passive"))
      (node (ref "c14") (pin "2") (pinfunction "2_2") (pintype "passive"))
      (node (ref "c6") (pin "2") (pinfunction "2_2") (pintype "passive"))
    )
    (net (code "3") (name "+5V{slash}+3V3") (class "Default")
      (node (ref "D5") (pin "1") (pinfunction "Cathode_1") (pintype "passive"))
      (node (ref "D6") (pin "1") (pinfunction "Cathode_1") (pintype "passive"))
      (node (ref "FB1") (pin "1") (pinfunction "1_1") (pintype "passive"))
      (node (ref "FB2") (pin "1") (pinfunction "1_1") (pintype "passive"))
      (node (ref "FB3") (pin "1") (pinfunction "1_1") (pintype "passive"))
      (node (ref "J1") (pin "2") (pinfunction "2_2") (pintype "passive"))
      (node (ref "J5") (pin "2") (pinfunction "2_2") (pintype "passive"))
      (node (ref "J6") (pin "2") (pinfunction "2_2") (pintype "passive"))
      (node (ref "JP4") (pin "2") (pinfunction "2_2") (pintype "passive"))
      (node (ref "R1") (pin "2") (pinfunction "2_2") (pintype "passive"))
      (node (ref "R14") (pin "2") (pinfunction "2_2") (pintype "passive"))
      (node (ref "R15") (pin "2") (pinfunction "2_2") (pintype "passive"))
      (node (ref "R17") (pin "1") (pinfunction "1_1") (pintype "passive"))
      (node (ref "R18") (pin "2") (pinfunction "2_2") (pintype "passive"))
      (node (ref "R19") (pin "2") (pinfunction "2_2") (pintype "passive"))
      (node (ref "R2") (pin "2") (pinfunction "2_2") (pintype "passive"))
      (node (ref "R20") (pin "2") (pinfunction "2_2") (pintype "passive"))
      (node (ref "R21") (pin "2") (pinfunction "2_2") (pintype "passive"))
      (node (ref "R27") (pin "2") (pinfunction "2_2") (pintype "passive"))
      (node (ref "R28") (pin "1") (pinfunction "1_1") (pintype "passive"))
      (node (ref "R3") (pin "2") (pinfunction "2_2") (pintype "passive"))
      (node (ref "R4") (pin "2") (pinfunction "2_2") (pintype "passive"))
      (node (ref "U4") (pin "5") (pinfunction "5_5") (pintype "passive"))
      (node (ref "U5") (pin "5") (pinfunction "5_5") (pintype "passive"))
      (node (ref "U6") (pin "5") (pinfunction "5_5") (pintype "passive"))
      (node (ref "U7") (pin "5") (pinfunction "5_5") (pintype "passive"))
      (node (ref "c15") (pin "2") (pinfunction "2_2") (pintype "passive"))
      (node (ref "c17") (pin "2") (pinfunction "2_2") (pintype "passive"))
      (node (ref "c26") (pin "2") (pinfunction "2_2") (pintype "passive"))
      (node (ref "c28") (pin "1") (pinfunction "1_1") (pintype "passive"))
      (node (ref "c29") (pin "1") (pinfunction "1_1") (pintype "passive"))
      (node (ref "c30") (pin "1") (pinfunction "1_1") (pintype "passive"))
      (node (ref "c34") (pin "2") (pinfunction "2_2") (pintype "passive"))
      (node (ref "c8") (pin "2") (pinfunction "2_2") (pintype "passive"))
    )
    (net (code "4") (name "+AREF") (class "Default")
      (node (ref "J4") (pin "8") (pinfunction "8_8") (pintype "passive"))
      (node (ref "U1") (pin "21") (pinfunction "AREF_21") (pintype "passive"))
      (node (ref "c21") (pin "2") (pinfunction "2_2") (pintype "passive"))
      (node (ref "c24") (pin "2") (pinfunction "2_2") (pintype "passive"))
    )
    (net (code "5") (name "/+3.3V_16U2_UCAP") (class "Default")
      (node (ref "C7") (pin "2") (pinfunction "2_2") (pintype "passive"))
      (node (ref "R26") (pin "1") (pinfunction "1_1") (pintype "passive"))
      (node (ref "U2") (pin "27") (pinfunction "UCAP_27") (pintype "passive"))
    )
    (net (code "6") (name "/+5V_USB") (class "Default")
      (node (ref "C1") (pin "1") (pinfunction "1_1") (pintype "passive"))
      (node (ref "J7") (pin "1") (pinfunction "1_1") (pintype "passive"))
      (node (ref "L1") (pin "1") (pinfunction "1_1") (pintype "passive"))
    )
    (net (code "7") (name "/+5V{slash}+3V3_16U2") (class "Default")
      (node (ref "FB1") (pin "2") (pinfunction "2_2") (pintype "passive"))
      (node (ref "R26") (pin "2") (pinfunction "2_2") (pintype "passive"))
      (node (ref "U2") (pin "32") (pinfunction "AVCC_32") (pintype "passive"))
      (node (ref "U2") (pin "4") (pinfunction "VCC_4") (pintype "passive"))
      (node (ref "c3") (pin "2") (pinfunction "2_2") (pintype "passive"))
      (node (ref "c4") (pin "2") (pinfunction "2_2") (pintype "passive"))
      (node (ref "c5") (pin "2") (pinfunction "2_2") (pintype "passive"))
    )
    (net (code "8") (name "/+5V{slash}+3V3_328P_AVCC") (class "Default")
      (node (ref "FB3") (pin "2") (pinfunction "2_2") (pintype "passive"))
      (node (ref "U1") (pin "20") (pinfunction "AVCC_20") (pintype "passive"))
      (node (ref "c22") (pin "2") (pinfunction "2_2") (pintype "passive"))
      (node (ref "c23") (pin "2") (pinfunction "2_2") (pintype "passive"))
    )
    (net (code "9") (name "/+5V{slash}+3V3_328P_VCC") (class "Default")
      (node (ref "FB2") (pin "2") (pinfunction "2_2") (pintype "passive"))
      (node (ref "U1") (pin "7") (pinfunction "VCC_7") (pintype "passive"))
      (node (ref "c19") (pin "2") (pinfunction "2_2") (pintype "passive"))
      (node (ref "c20") (pin "2") (pinfunction "2_2") (pintype "passive"))
    )
    (net (code "10") (name "/16U2-RESET") (class "Default")
      (node (ref "JP3") (pin "4") (pinfunction "4_4") (pintype "passive"))
      (node (ref "R4") (pin "1") (pinfunction "1_1") (pintype "passive"))
      (node (ref "U2") (pin "24") (pinfunction "Reset_(PC1_/_dW)_24") (pintype "passive"))
      (node (ref "U5") (pin "4") (pinfunction "4_4") (pintype "passive"))
    )
    (net (code "11") (name "/16U2PROG_328P_RESETn") (class "Default")
      (node (ref "JP1") (pin "2") (pinfunction "2_2") (pintype "passive"))
      (node (ref "R1") (pin "1") (pinfunction "1_1") (pintype "passive"))
      (node (ref "U2") (pin "13") (pinfunction "/_HWB_/_AIN6_/_T0_/_INT7)_PD7_13") (pintype "passive"))
    )
    (net (code "12") (name "/16U2_16MHZ_XTAL1") (class "Default")
      (node (ref "C10") (pin "2") (pinfunction "2_2") (pintype "passive"))
      (node (ref "R9") (pin "1") (pinfunction "1_1") (pintype "passive"))
      (node (ref "U2") (pin "1") (pinfunction "XTAL1_1") (pintype "passive"))
      (node (ref "Y2") (pin "1") (pinfunction "1_1") (pintype "passive"))
    )
    (net (code "13") (name "/16U2_16MHZ_XTAL2") (class "Default")
      (node (ref "C9") (pin "2") (pinfunction "2_2") (pintype "passive"))
      (node (ref "R9") (pin "2") (pinfunction "2_2") (pintype "passive"))
      (node (ref "U2") (pin "2") (pinfunction "(PC0)_XTAL2_2") (pintype "passive"))
      (node (ref "Y2") (pin "2") (pinfunction "2_2") (pintype "passive"))
    )
    (net (code "14") (name "/16U2_BUF_RESETn") (class "Default")
      (node (ref "R23") (pin "2") (pinfunction "2_2") (pintype "passive"))
      (node (ref "U5") (pin "1") (pinfunction "1_1") (pintype "passive"))
      (node (ref "U5") (pin "2") (pinfunction "2_2") (pintype "passive"))
      (node (ref "c31") (pin "2") (pinfunction "2_2") (pintype "passive"))
    )
    (net (code "15") (name "/16U2_HDR_RESETn") (class "Default")
      (node (ref "J6") (pin "5") (pinfunction "5_5") (pintype "passive"))
      (node (ref "JP3") (pin "3") (pinfunction "3_3") (pintype "passive"))
    )
    (net (code "16") (name "/16U2_MISO") (class "Default")
      (node (ref "J6") (pin "1") (pinfunction "1_1") (pintype "passive"))
      (node (ref "U2") (pin "17") (pinfunction "PB3_(PDO_/_MISO_/_PCINT3)_17") (pintype "passive"))
    )
    (net (code "17") (name "/16U2_MOSI") (class "Default")
      (node (ref "J6") (pin "4") (pinfunction "4_4") (pintype "passive"))
      (node (ref "U2") (pin "16") (pinfunction "(PDI_/_MOSI_/_PCINT2)_PB2_16") (pintype "passive"))
    )
    (net (code "18") (name "/16U2_PB4") (class "Default")
      (node (ref "JP2") (pin "1") (pinfunction "1_1") (pintype "passive"))
      (node (ref "JP3") (pin "2") (pinfunction "2_2") (pintype "passive"))
      (node (ref "U2") (pin "18") (pinfunction "PB4_(T1_/_PCINT4)_18") (pintype "passive"))
    )
    (net (code "19") (name "/16U2_PB5") (class "Default")
      (node (ref "JP2") (pin "3") (pinfunction "3_3") (pintype "passive"))
      (node (ref "U2") (pin "19") (pinfunction "PB5_(PCINT5)_19") (pintype "passive"))
    )
    (net (code "20") (name "/16U2_PB6") (class "Default")
      (node (ref "JP2") (pin "2") (pinfunction "2_2") (pintype "passive"))
      (node (ref "U2") (pin "20") (pinfunction "PB6_(PCINT6)_20") (pintype "passive"))
    )
    (net (code "21") (name "/16U2_PB7") (class "Default")
      (node (ref "JP2") (pin "4") (pinfunction "4_4") (pintype "passive"))
      (node (ref "U2") (pin "21") (pinfunction "PB7_(PCINT7_/_OC.0A_/_OC.1C)_21") (pintype "passive"))
    )
    (net (code "22") (name "/16U2_RXD") (class "Default")
      (node (ref "R11") (pin "1") (pinfunction "1_1") (pintype "passive"))
      (node (ref "U2") (pin "8") (pinfunction "(RXD1_/_AIN1_/_INT2)_PD2_8") (pintype "passive"))
    )
    (net (code "23") (name "/16U2_RX_LED") (class "Default")
      (node (ref "D4") (pin "1") (pinfunction "Cathode_1") (pintype "passive"))
      (node (ref "U2") (pin "10") (pinfunction "INT5/_AIN3)_PD4_10") (pintype "passive"))
    )
    (net (code "24") (name "/16U2_SCLK") (class "Default")
      (node (ref "J6") (pin "3") (pinfunction "3_3") (pintype "passive"))
      (node (ref "R5") (pin "2") (pinfunction "2_2") (pintype "passive"))
    )
    (net (code "25") (name "/16U2_SCLK_R") (class "Default")
      (node (ref "R5") (pin "1") (pinfunction "1_1") (pintype "passive"))
      (node (ref "U2") (pin "15") (pinfunction "SCLK_/_PCINT1)_PB1_15") (pintype "passive"))
    )
    (net (code "26") (name "/16U2_TXD") (class "Default")
      (node (ref "R10") (pin "1") (pinfunction "1_1") (pintype "passive"))
      (node (ref "U2") (pin "9") (pinfunction "TXD1_/_INT3)_PD3_9") (pintype "passive"))
    )
    (net (code "27") (name "/16U2_TX_LED") (class "Default")
      (node (ref "D3") (pin "1") (pinfunction "Cathode_1") (pintype "passive"))
      (node (ref "U2") (pin "11") (pinfunction "XCK_AIN4_/_PCINT12)_PD5_11") (pintype "passive"))
    )
    (net (code "28") (name "/328P-Auto_Resetn") (class "Default")
      (node (ref "R18") (pin "1") (pinfunction "1_1") (pintype "passive"))
      (node (ref "U6") (pin "1") (pinfunction "1_1") (pintype "passive"))
      (node (ref "c11") (pin "1") (pinfunction "1_1") (pintype "passive"))
    )
    (net (code "29") (name "/328P-Buf_Resetn") (class "Default")
      (node (ref "R24") (pin "2") (pinfunction "2_2") (pintype "passive"))
      (node (ref "U6") (pin "2") (pinfunction "2_2") (pintype "passive"))
      (node (ref "c32") (pin "2") (pinfunction "2_2") (pintype "passive"))
    )
    (net (code "30") (name "/328P-RESET") (class "Default")
      (node (ref "J1") (pin "3") (pinfunction "3_3") (pintype "passive"))
      (node (ref "J5") (pin "5") (pinfunction "5_5") (pintype "passive"))
      (node (ref "JP3") (pin "1") (pinfunction "1_1") (pintype "passive"))
      (node (ref "R14") (pin "1") (pinfunction "1_1") (pintype "passive"))
      (node (ref "U1") (pin "1") (pinfunction "(PCINT14/~{RESET})_PC6_1") (pintype "passive"))
      (node (ref "U6") (pin "4") (pinfunction "4_4") (pintype "passive"))
    )
    (net (code "31") (name "/328P_16MHZ_XTAL1") (class "Default")
      (node (ref "C27") (pin "2") (pinfunction "2_2") (pintype "passive"))
      (node (ref "R16") (pin "1") (pinfunction "1_1") (pintype "passive"))
      (node (ref "U1") (pin "9") (pinfunction "(PCINT6/XTAL1/TOSC1)_PB6_9") (pintype "passive"))
      (node (ref "Y1") (pin "1") (pinfunction "1_1") (pintype "passive"))
    )
    (net (code "32") (name "/328P_16MHZ_XTAL2") (class "Default")
      (node (ref "C25") (pin "2") (pinfunction "2_2") (pintype "passive"))
      (node (ref "R16") (pin "2") (pinfunction "2_2") (pintype "passive"))
      (node (ref "U1") (pin "10") (pinfunction "(PCINT7/XTAL2/TOSC2)_PB7_10") (pintype "passive"))
      (node (ref "Y1") (pin "2") (pinfunction "2_2") (pintype "passive"))
    )
    (net (code "33") (name "/AD0") (class "Default")
      (node (ref "J2") (pin "1") (pinfunction "1_1") (pintype "passive"))
      (node (ref "U1") (pin "23") (pinfunction "PC0_(ADC0/PCINT8)_23") (pintype "passive"))
    )
    (net (code "34") (name "/AD1") (class "Default")
      (node (ref "J2") (pin "2") (pinfunction "2_2") (pintype "passive"))
      (node (ref "U1") (pin "24") (pinfunction "PC1_(ADC1/PCINT9)_24") (pintype "passive"))
    )
    (net (code "35") (name "/AD2") (class "Default")
      (node (ref "J2") (pin "3") (pinfunction "3_3") (pintype "passive"))
      (node (ref "U1") (pin "25") (pinfunction "PC2_(ADC2/PCINT10)_25") (pintype "passive"))
    )
    (net (code "36") (name "/AD3") (class "Default")
      (node (ref "J2") (pin "4") (pinfunction "4_4") (pintype "passive"))
      (node (ref "U1") (pin "26") (pinfunction "PC3_(ADC3/PCINT11)_26") (pintype "passive"))
    )
    (net (code "37") (name "/AD4{slash}SDA") (class "Default")
      (node (ref "J2") (pin "5") (pinfunction "5_5") (pintype "passive"))
      (node (ref "J4") (pin "9") (pinfunction "9_9") (pintype "passive"))
      (node (ref "U1") (pin "27") (pinfunction "PC4_(ADC4/SDA/PCINT12)_27") (pintype "passive"))
    )
    (net (code "38") (name "/AD5{slash}SCL") (class "Default")
      (node (ref "J2") (pin "6") (pinfunction "6_6") (pintype "passive"))
      (node (ref "J4") (pin "10") (pinfunction "10_10") (pintype "passive"))
      (node (ref "U1") (pin "28") (pinfunction "PC5_(ADC5/SCL/PCINT13)_28") (pintype "passive"))
    )
    (net (code "39") (name "/BUTTON_RESETn") (class "Default")
      (node (ref "D6") (pin "2") (pinfunction "Anode_2") (pintype "passive"))
      (node (ref "R20") (pin "1") (pinfunction "1_1") (pintype "passive"))
      (node (ref "R24") (pin "1") (pinfunction "1_1") (pintype "passive"))
      (node (ref "SW1") (pin "1") (pinfunction "1_1") (pintype "passive"))
      (node (ref "SW1") (pin "2") (pinfunction "2_2") (pintype "passive"))
    )
    (net (code "40") (name "/CON_USB_N") (class "Default")
      (node (ref "J7") (pin "2") (pinfunction "2_2") (pintype "passive"))
      (node (ref "R6") (pin "1") (pinfunction "1_1") (pintype "passive"))
      (node (ref "Z2") (pin "2") (pinfunction "2_2") (pintype "passive"))
    )
    (net (code "41") (name "/CON_USB_P") (class "Default")
      (node (ref "J7") (pin "3") (pinfunction "3_3") (pintype "passive"))
      (node (ref "R7") (pin "1") (pinfunction "1_1") (pintype "passive"))
      (node (ref "Z1") (pin "2") (pinfunction "2_2") (pintype "passive"))
    )
    (net (code "42") (name "/IO0") (class "Default")
      (node (ref "J3") (pin "1") (pinfunction "1_1") (pintype "passive"))
      (node (ref "R10") (pin "2") (pinfunction "2_2") (pintype "passive"))
      (node (ref "U1") (pin "2") (pinfunction "(PCINT16/RXD)_PD0_2") (pintype "passive"))
    )
    (net (code "43") (name "/IO1") (class "Default")
      (node (ref "J3") (pin "2") (pinfunction "2_2") (pintype "passive"))
      (node (ref "R11") (pin "2") (pinfunction "2_2") (pintype "passive"))
      (node (ref "U1") (pin "3") (pinfunction "(PCINT17/TXD)_PD1_3") (pintype "passive"))
    )
    (net (code "44") (name "/IO2") (class "Default")
      (node (ref "J3") (pin "3") (pinfunction "3_3") (pintype "passive"))
      (node (ref "U1") (pin "4") (pinfunction "(PCINT18/INT0)_PD2_4") (pintype "passive"))
    )
    (net (code "45") (name "/IO3") (class "Default")
      (node (ref "J3") (pin "4") (pinfunction "4_4") (pintype "passive"))
      (node (ref "U1") (pin "5") (pinfunction "(PCINT19/OC2B/INT1)_PD3_5") (pintype "passive"))
    )
    (net (code "46") (name "/IO4") (class "Default")
      (node (ref "J3") (pin "5") (pinfunction "5_5") (pintype "passive"))
      (node (ref "U1") (pin "6") (pinfunction "(PCINT20/XCK/T0)_PD4_6") (pintype "passive"))
    )
    (net (code "47") (name "/IO5") (class "Default")
      (node (ref "J3") (pin "6") (pinfunction "6_6") (pintype "passive"))
      (node (ref "U1") (pin "11") (pinfunction "(PCINT21/OC0B/T1)_PD5_11") (pintype "passive"))
    )
    (net (code "48") (name "/IO6") (class "Default")
      (node (ref "J3") (pin "7") (pinfunction "7_7") (pintype "passive"))
      (node (ref "U1") (pin "12") (pinfunction "(PCINT22/OC0A/AIN0)_PD6_12") (pintype "passive"))
    )
    (net (code "49") (name "/IO7") (class "Default")
      (node (ref "J3") (pin "8") (pinfunction "8_8") (pintype "passive"))
      (node (ref "U1") (pin "13") (pinfunction "(PCINT23/AIN1)_PD7_13") (pintype "passive"))
    )
    (net (code "50") (name "/IO8") (class "Default")
      (node (ref "J4") (pin "1") (pinfunction "1_1") (pintype "passive"))
      (node (ref "R22") (pin "2") (pinfunction "2_2") (pintype "passive"))
      (node (ref "U1") (pin "14") (pinfunction "(PCINT0/CLKO/ICP1)_PB0_14") (pintype "passive"))
    )
    (net (code "51") (name "/IO9") (class "Default")
      (node (ref "J4") (pin "2") (pinfunction "2_2") (pintype "passive"))
      (node (ref "U1") (pin "15") (pinfunction "PB1_(OC1A/PCINT1)_15") (pintype "passive"))
    )
    (net (code "52") (name "/MISO") (class "Default")
      (node (ref "J4") (pin "5") (pinfunction "5_5") (pintype "passive"))
      (node (ref "J5") (pin "1") (pinfunction "1_1") (pintype "passive"))
      (node (ref "U1") (pin "18") (pinfunction "PB4_(MISO/PCINT4)_18") (pintype "passive"))
    )
    (net (code "53") (name "/MOSI") (class "Default")
      (node (ref "J4") (pin "4") (pinfunction "4_4") (pintype "passive"))
      (node (ref "J5") (pin "4") (pinfunction "4_4") (pintype "passive"))
      (node (ref "U1") (pin "17") (pinfunction "PB3_(MOSI/OC2A/PCINT3)_17") (pintype "passive"))
    )
    (net (code "54") (name "/SCK") (class "Default")
      (node (ref "J4") (pin "6") (pinfunction "6_6") (pintype "passive"))
      (node (ref "J5") (pin "3") (pinfunction "3_3") (pintype "passive"))
      (node (ref "R13") (pin "2") (pinfunction "2_2") (pintype "passive"))
      (node (ref "U4") (pin "1") (pinfunction "1_1") (pintype "passive"))
      (node (ref "U4") (pin "2") (pinfunction "2_2") (pintype "passive"))
    )
    (net (code "55") (name "/SCK_R") (class "Default")
      (node (ref "R13") (pin "1") (pinfunction "1_1") (pintype "passive"))
      (node (ref "U1") (pin "19") (pinfunction "PB5_(SCK/PCINT5)_19") (pintype "passive"))
    )
    (net (code "56") (name "/SS") (class "Default")
      (node (ref "J4") (pin "3") (pinfunction "3_3") (pintype "passive"))
      (node (ref "U1") (pin "16") (pinfunction "PB2_(SS/OC1B/PCINT2)_16") (pintype "passive"))
    )
    (net (code "57") (name "/USB_N") (class "Default")
      (node (ref "R6") (pin "2") (pinfunction "2_2") (pintype "passive"))
      (node (ref "U2") (pin "30") (pinfunction "D-_30") (pintype "passive"))
    )
    (net (code "58") (name "/USB_P") (class "Default")
      (node (ref "R7") (pin "2") (pinfunction "2_2") (pintype "passive"))
      (node (ref "U2") (pin "29") (pinfunction "D+_29") (pintype "passive"))
    )
    (net (code "59") (name "/USER_BUTTON") (class "Default")
      (node (ref "R21") (pin "1") (pinfunction "1_1") (pintype "passive"))
      (node (ref "R25") (pin "1") (pinfunction "1_1") (pintype "passive"))
      (node (ref "SW2") (pin "1") (pinfunction "1_1") (pintype "passive"))
      (node (ref "SW2") (pin "2") (pinfunction "2_2") (pintype "passive"))
    )
    (net (code "60") (name "/USER_BUTTON_BUF") (class "Default")
      (node (ref "R25") (pin "2") (pinfunction "2_2") (pintype "passive"))
      (node (ref "U7") (pin "1") (pinfunction "1_1") (pintype "passive"))
      (node (ref "U7") (pin "2") (pinfunction "2_2") (pintype "passive"))
      (node (ref "c33") (pin "2") (pinfunction "2_2") (pintype "passive"))
    )
    (net (code "61") (name "GND") (class "Default")
      (node (ref "C1") (pin "2") (pinfunction "2_2") (pintype "passive"))
      (node (ref "C10") (pin "1") (pinfunction "1_1") (pintype "passive"))
      (node (ref "C2") (pin "2") (pinfunction "2_2") (pintype "passive"))
      (node (ref "C25") (pin "1") (pinfunction "1_1") (pintype "passive"))
      (node (ref "C27") (pin "1") (pinfunction "1_1") (pintype "passive"))
      (node (ref "C7") (pin "1") (pinfunction "1_1") (pintype "passive"))
      (node (ref "C9") (pin "1") (pinfunction "1_1") (pintype "passive"))
      (node (ref "D1") (pin "1") (pinfunction "Cathode_1") (pintype "passive"))
      (node (ref "J1") (pin "6") (pinfunction "6_6") (pintype "passive"))
      (node (ref "J1") (pin "7") (pinfunction "7_7") (pintype "passive"))
      (node (ref "J4") (pin "7") (pinfunction "7_7") (pintype "passive"))
      (node (ref "J5") (pin "6") (pinfunction "6_6") (pintype "passive"))
      (node (ref "J6") (pin "6") (pinfunction "6_6") (pintype "passive"))
      (node (ref "J7") (pin "10") (pinfunction "10_10") (pintype "passive"))
      (node (ref "J7") (pin "11") (pinfunction "11_11") (pintype "passive"))
      (node (ref "J7") (pin "5") (pinfunction "5_5") (pintype "passive"))
      (node (ref "J7") (pin "6") (pinfunction "6_6") (pintype "passive"))
      (node (ref "J7") (pin "7") (pinfunction "7_7") (pintype "passive"))
      (node (ref "J7") (pin "8") (pinfunction "8_8") (pintype "passive"))
      (node (ref "J7") (pin "9") (pinfunction "9_9") (pintype "passive"))
      (node (ref "J9") (pin "1") (pinfunction "1_1") (pintype "open_collector"))
      (node (ref "MH1") (pin "1") (pinfunction "1_1") (pintype "passive"))
      (node (ref "MH2") (pin "1") (pinfunction "1_1") (pintype "passive"))
      (node (ref "MH3") (pin "1") (pinfunction "1_1") (pintype "passive"))
      (node (ref "R12") (pin "1") (pinfunction "1_1") (pintype "passive"))
      (node (ref "R8") (pin "1") (pinfunction "1_1") (pintype "passive"))
      (node (ref "SW1") (pin "3") (pinfunction "3_3") (pintype "passive"))
      (node (ref "SW1") (pin "4") (pinfunction "4_4") (pintype "passive"))
      (node (ref "SW2") (pin "3") (pinfunction "3_3") (pintype "passive"))
      (node (ref "SW2") (pin "4") (pinfunction "4_4") (pintype "passive"))
      (node (ref "U1") (pin "22") (pinfunction "GND_22") (pintype "passive"))
      (node (ref "U1") (pin "8") (pinfunction "GND_8") (pintype "passive"))
      (node (ref "U3") (pin "3") (pinfunction "GND_3") (pintype "passive"))
      (node (ref "U3") (pin "6") (pinfunction "EPAD_6") (pintype "passive"))
      (node (ref "U4") (pin "3") (pinfunction "3_3") (pintype "passive"))
      (node (ref "U5") (pin "3") (pinfunction "3_3") (pintype "passive"))
      (node (ref "U6") (pin "3") (pinfunction "3_3") (pintype "passive"))
      (node (ref "U7") (pin "3") (pinfunction "3_3") (pintype "passive"))
      (node (ref "Z1") (pin "1") (pinfunction "1_1") (pintype "passive"))
      (node (ref "Z2") (pin "1") (pinfunction "1_1") (pintype "passive"))
      (node (ref "c12") (pin "2") (pinfunction "2_2") (pintype "passive"))
      (node (ref "c13") (pin "2") (pinfunction "2_2") (pintype "passive"))
      (node (ref "c14") (pin "1") (pinfunction "1_1") (pintype "passive"))
      (node (ref "c15") (pin "1") (pinfunction "1_1") (pintype "passive"))
      (node (ref "c16") (pin "1") (pinfunction "1_1") (pintype "passive"))
      (node (ref "c17") (pin "1") (pinfunction "1_1") (pintype "passive"))
      (node (ref "c19") (pin "1") (pinfunction "1_1") (pintype "passive"))
      (node (ref "c20") (pin "1") (pinfunction "1_1") (pintype "passive"))
      (node (ref "c21") (pin "1") (pinfunction "1_1") (pintype "passive"))
      (node (ref "c22") (pin "1") (pinfunction "1_1") (pintype "passive"))
      (node (ref "c23") (pin "1") (pinfunction "1_1") (pintype "passive"))
      (node (ref "c24") (pin "1") (pinfunction "1_1") (pintype "passive"))
      (node (ref "c26") (pin "1") (pinfunction "1_1") (pintype "passive"))
      (node (ref "c28") (pin "2") (pinfunction "2_2") (pintype "passive"))
      (node (ref "c29") (pin "2") (pinfunction "2_2") (pintype "passive"))
      (node (ref "c3") (pin "1") (pinfunction "1_1") (pintype "passive"))
      (node (ref "c30") (pin "2") (pinfunction "2_2") (pintype "passive"))
      (node (ref "c31") (pin "1") (pinfunction "1_1") (pintype "passive"))
      (node (ref "c32") (pin "1") (pinfunction "1_1") (pintype "passive"))
      (node (ref "c33") (pin "1") (pinfunction "1_1") (pintype "passive"))
      (node (ref "c34") (pin "1") (pinfunction "1_1") (pintype "passive"))
      (node (ref "c4") (pin "1") (pinfunction "1_1") (pintype "passive"))
      (node (ref "c5") (pin "1") (pinfunction "1_1") (pintype "passive"))
      (node (ref "c6") (pin "1") (pinfunction "1_1") (pintype "passive"))
      (node (ref "c8") (pin "1") (pinfunction "1_1") (pintype "passive"))
    )
    (net (code "62") (name "Net-(D1-Anode)") (class "Default")
      (node (ref "D1") (pin "2") (pinfunction "Anode_2") (pintype "passive"))
      (node (ref "R17") (pin "2") (pinfunction "2_2") (pintype "passive"))
    )
    (net (code "63") (name "Net-(D2-Anode)") (class "Default")
      (node (ref "D2") (pin "2") (pinfunction "Anode_2") (pintype "passive"))
      (node (ref "R15") (pin "1") (pinfunction "1_1") (pintype "passive"))
    )
    (net (code "64") (name "Net-(D2-Cathode)") (class "Default")
      (node (ref "D2") (pin "1") (pinfunction "Cathode_1") (pintype "passive"))
      (node (ref "U4") (pin "4") (pinfunction "4_4") (pintype "passive"))
    )
    (net (code "65") (name "Net-(D3-Anode)") (class "Default")
      (node (ref "D3") (pin "2") (pinfunction "Anode_2") (pintype "passive"))
      (node (ref "R2") (pin "1") (pinfunction "1_1") (pintype "passive"))
    )
    (net (code "66") (name "Net-(D4-Anode)") (class "Default")
      (node (ref "D4") (pin "2") (pinfunction "Anode_2") (pintype "passive"))
      (node (ref "R3") (pin "1") (pinfunction "1_1") (pintype "passive"))
    )
    (net (code "67") (name "Net-(D5-Anode)") (class "Default")
      (node (ref "D5") (pin "2") (pinfunction "Anode_2") (pintype "passive"))
      (node (ref "R19") (pin "1") (pinfunction "1_1") (pintype "passive"))
      (node (ref "R23") (pin "1") (pinfunction "1_1") (pintype "passive"))
    )
    (net (code "68") (name "Net-(J7-Pad4)") (class "Default")
      (node (ref "J7") (pin "4") (pinfunction "4_4") (pintype "passive"))
      (node (ref "R8") (pin "2") (pinfunction "2_2") (pintype "passive"))
    )
    (net (code "69") (name "Net-(JP1-Pad1)") (class "Default")
      (node (ref "JP1") (pin "1") (pinfunction "1_1") (pintype "passive"))
      (node (ref "c11") (pin "2") (pinfunction "2_2") (pintype "passive"))
    )
    (net (code "70") (name "Net-(JP1-Pad3)") (class "Default")
      (node (ref "JP1") (pin "3") (pinfunction "3_3") (pintype "passive"))
      (node (ref "R12") (pin "2") (pinfunction "2_2") (pintype "passive"))
    )
    (net (code "71") (name "Net-(R22-Pad1)") (class "Default")
      (node (ref "R22") (pin "1") (pinfunction "1_1") (pintype "passive"))
      (node (ref "U7") (pin "4") (pinfunction "4_4") (pintype "passive"))
    )
    (net (code "72") (name "unconnected-(J1-Pad1)") (class "Default")
      (node (ref "J1") (pin "1") (pinfunction "1_1") (pintype "passive+no_connect"))
    )
    (net (code "73") (name "unconnected-(J1-Pad8)") (class "Default")
      (node (ref "J1") (pin "8") (pinfunction "8_8") (pintype "passive+no_connect"))
    )
    (net (code "74") (name "unconnected-(MH4-Pad1)") (class "Default")
      (node (ref "MH4") (pin "1") (pinfunction "1_1") (pintype "passive+no_connect"))
    )
    (net (code "75") (name "unconnected-(U2-(AIN0_{slash}_INT1)_PD1-Pad7)") (class "Default")
      (node (ref "U2") (pin "7") (pinfunction "(AIN0_/_INT1)_PD1_7") (pintype "passive"))
    )
    (net (code "76") (name "unconnected-(U2-(OC.0B_{slash}_INT0)_PD0-Pad6)") (class "Default")
      (node (ref "U2") (pin "6") (pinfunction "(OC.0B_/_INT0)_PD0_6") (pintype "passive"))
    )
    (net (code "77") (name "unconnected-(U2-(PCINT11_{slash}AIN2_)_PC2-Pad5)") (class "Default")
      (node (ref "U2") (pin "5") (pinfunction "(PCINT11_/AIN2_)_PC2_5") (pintype "passive+no_connect"))
    )
    (net (code "78") (name "unconnected-(U2-GND-Pad3)") (class "Default")
      (node (ref "U2") (pin "3") (pinfunction "GND_3") (pintype "passive"))
    )
    (net (code "79") (name "unconnected-(U2-PC4_(PCINT10)-Pad26)") (class "Default")
      (node (ref "U2") (pin "26") (pinfunction "PC4_(PCINT10)_26") (pintype "passive+no_connect"))
    )
    (net (code "80") (name "unconnected-(U2-PC5_(_PCINT9{slash}_OC.1B)-Pad25)") (class "Default")
      (node (ref "U2") (pin "25") (pinfunction "PC5_(_PCINT9/_OC.1B)_25") (pintype "passive+no_connect"))
    )
    (net (code "81") (name "unconnected-(U2-PC6_(OC.1A_{slash}_PCINT8)-Pad23)") (class "Default")
      (node (ref "U2") (pin "23") (pinfunction "PC6_(OC.1A_/_PCINT8)_23") (pintype "passive+no_connect"))
    )
    (net (code "82") (name "unconnected-(U2-PC7_(INT4_{slash}_ICP1_{slash}_CLKO)-Pad22)") (class "Default")
      (node (ref "U2") (pin "22") (pinfunction "PC7_(INT4_/_ICP1_/_CLKO)_22") (pintype "passive+no_connect"))
    )
    (net (code "83") (name "unconnected-(U2-RTS_{slash}_AIN5_{slash}_INT6)_PD6-Pad12)") (class "Default")
      (node (ref "U2") (pin "12") (pinfunction "RTS_/_AIN5_/_INT6)_PD6_12") (pintype "passive+no_connect"))
    )
    (net (code "84") (name "unconnected-(U2-SS_{slash}_PCINT0)_PB0-Pad14)") (class "Default")
      (node (ref "U2") (pin "14") (pinfunction "SS_/_PCINT0)_PB0_14") (pintype "passive+no_connect"))
    )
    (net (code "85") (name "unconnected-(U2-UGND-Pad28)") (class "Default")
      (node (ref "U2") (pin "28") (pinfunction "UGND_28") (pintype "passive"))
    )
  )
)
